# lirc.net
KiCad netlist of a schematic drawn in EAGLE
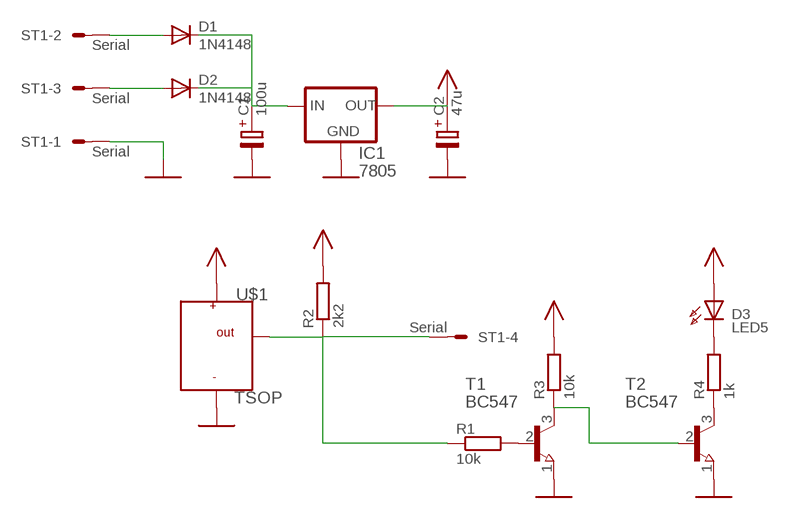
[diagram p0: schematic, sheet 1]

(export (version "E")
  (design (tool "Eeschema 10.0.6"))
  (components
    (comp (ref "C1")
      (value "100u")
      (footprint "eagle-import:E30-10")
      (libsource (lib "eagle-import") (part "E30-10"))
    )
    (comp (ref "C2")
      (value "47u")
      (footprint "eagle-import:E25-10")
      (libsource (lib "eagle-import") (part "E25-10"))
    )
    (comp (ref "D1")
      (value "1N4148")
      (footprint "eagle-import:DO35-10")
      (libsource (lib "eagle-import") (part "1N4148"))
    )
    (comp (ref "D2")
      (value "1N4148")
      (footprint "eagle-import:DO35-10")
      (libsource (lib "eagle-import") (part "1N4148"))
    )
    (comp (ref "D3")
      (value "LED5")
      (footprint "eagle-import:LED5")
      (libsource (lib "eagle-import") (part "LED5"))
    )
    (comp (ref "IC1")
      (value "7805")
      (footprint "eagle-import:78XXS")
      (libsource (lib "eagle-import") (part "78XXS"))
    )
    (comp (ref "R1")
      (value "10k")
      (footprint "eagle-import:0207_10")
      (libsource (lib "eagle-import") (part "0207/10"))
    )
    (comp (ref "R2")
      (value "2k2")
      (footprint "eagle-import:0207_10")
      (libsource (lib "eagle-import") (part "0207/10"))
    )
    (comp (ref "R3")
      (value "10k")
      (footprint "eagle-import:0207_10")
      (libsource (lib "eagle-import") (part "0207/10"))
    )
    (comp (ref "R4")
      (value "1k")
      (footprint "eagle-import:0207_10")
      (libsource (lib "eagle-import") (part "0207/10"))
    )
    (comp (ref "ST1")
      (value "Serial")
      (footprint "eagle-import:MSF4")
      (libsource (lib "eagle-import") (part "MSF4"))
    )
    (comp (ref "T1")
      (value "BC547")
      (footprint "eagle-import:TO92")
      (libsource (lib "eagle-import") (part "BC547"))
    )
    (comp (ref "T2")
      (value "BC547")
      (footprint "eagle-import:TO92")
      (libsource (lib "eagle-import") (part "BC547"))
    )
    (comp (ref "U$1")
      (value "TSOP")
      (footprint "eagle-import:TSOP")
      (libsource (lib "eagle-import") (part "TSOP"))
    )
  )
  (nets
    (net (code "1") (name "GND") (class "Default")
      (node (ref "C1") (pin "-") (pinfunction "-_-") (pintype "passive"))
      (node (ref "C2") (pin "-") (pinfunction "-_-") (pintype "passive"))
      (node (ref "IC1") (pin "GND") (pinfunction "GND_GND") (pintype "input"))
      (node (ref "ST1") (pin "1") (pinfunction "S_1") (pintype "passive"))
      (node (ref "T1") (pin "1") (pinfunction "E_1") (pintype "passive"))
      (node (ref "T2") (pin "1") (pinfunction "E_1") (pintype "passive"))
      (node (ref "U$1") (pin "-") (pinfunction "-_-") (pintype "passive"))
    )
    (net (code "2") (name "Net-(C1-Pad+)") (class "Default")
      (node (ref "C1") (pin "+") (pinfunction "+_+") (pintype "passive"))
      (node (ref "D1") (pin "K") (pinfunction "K_K") (pintype "passive"))
      (node (ref "D2") (pin "K") (pinfunction "K_K") (pintype "passive"))
      (node (ref "IC1") (pin "IN") (pinfunction "IN_IN") (pintype "input"))
    )
    (net (code "3") (name "Net-(D3-PadK)") (class "Default")
      (node (ref "D3") (pin "K") (pinfunction "K_K") (pintype "passive"))
      (node (ref "R4") (pin "2") (pinfunction "2_2") (pintype "passive"))
    )
    (net (code "4") (name "Net-(ST1B-S)") (class "Default")
      (node (ref "D1") (pin "A") (pinfunction "A_A") (pintype "passive"))
      (node (ref "ST1") (pin "2") (pinfunction "S_2") (pintype "passive"))
    )
    (net (code "5") (name "Net-(ST1C-S)") (class "Default")
      (node (ref "D2") (pin "A") (pinfunction "A_A") (pintype "passive"))
      (node (ref "ST1") (pin "3") (pinfunction "S_3") (pintype "passive"))
    )
    (net (code "6") (name "Net-(ST1D-S)") (class "Default")
      (node (ref "R1") (pin "1") (pinfunction "1_1") (pintype "passive"))
      (node (ref "R2") (pin "1") (pinfunction "1_1") (pintype "passive"))
      (node (ref "ST1") (pin "4") (pinfunction "S_4") (pintype "passive"))
      (node (ref "U$1") (pin "OUT") (pinfunction "OUT_OUT") (pintype "passive"))
    )
    (net (code "7") (name "Net-(T1-B)") (class "Default")
      (node (ref "R1") (pin "2") (pinfunction "2_2") (pintype "passive"))
      (node (ref "T1") (pin "2") (pinfunction "B_2") (pintype "passive"))
    )
    (net (code "8") (name "Net-(T1-C)") (class "Default")
      (node (ref "R3") (pin "1") (pinfunction "1_1") (pintype "passive"))
      (node (ref "T1") (pin "3") (pinfunction "C_3") (pintype "passive"))
      (node (ref "T2") (pin "2") (pinfunction "B_2") (pintype "passive"))
    )
    (net (code "9") (name "Net-(T2-C)") (class "Default")
      (node (ref "R4") (pin "1") (pinfunction "1_1") (pintype "passive"))
      (node (ref "T2") (pin "3") (pinfunction "C_3") (pintype "passive"))
    )
    (net (code "10") (name "VCC") (class "Default")
      (node (ref "C2") (pin "+") (pinfunction "+_+") (pintype "passive"))
      (node (ref "D3") (pin "A") (pinfunction "A_A") (pintype "passive"))
      (node (ref "IC1") (pin "OUT") (pinfunction "OUT_OUT") (pintype "passive"))
      (node (ref "R2") (pin "2") (pinfunction "2_2") (pintype "passive"))
      (node (ref "R3") (pin "2") (pinfunction "2_2") (pintype "passive"))
      (node (ref "U$1") (pin "+") (pinfunction "+_+") (pintype "passive"))
    )
  )
)
